# Shutdown_2019_v1_1_Power.net
KiCad netlist of a schematic drawn in Altium Designer
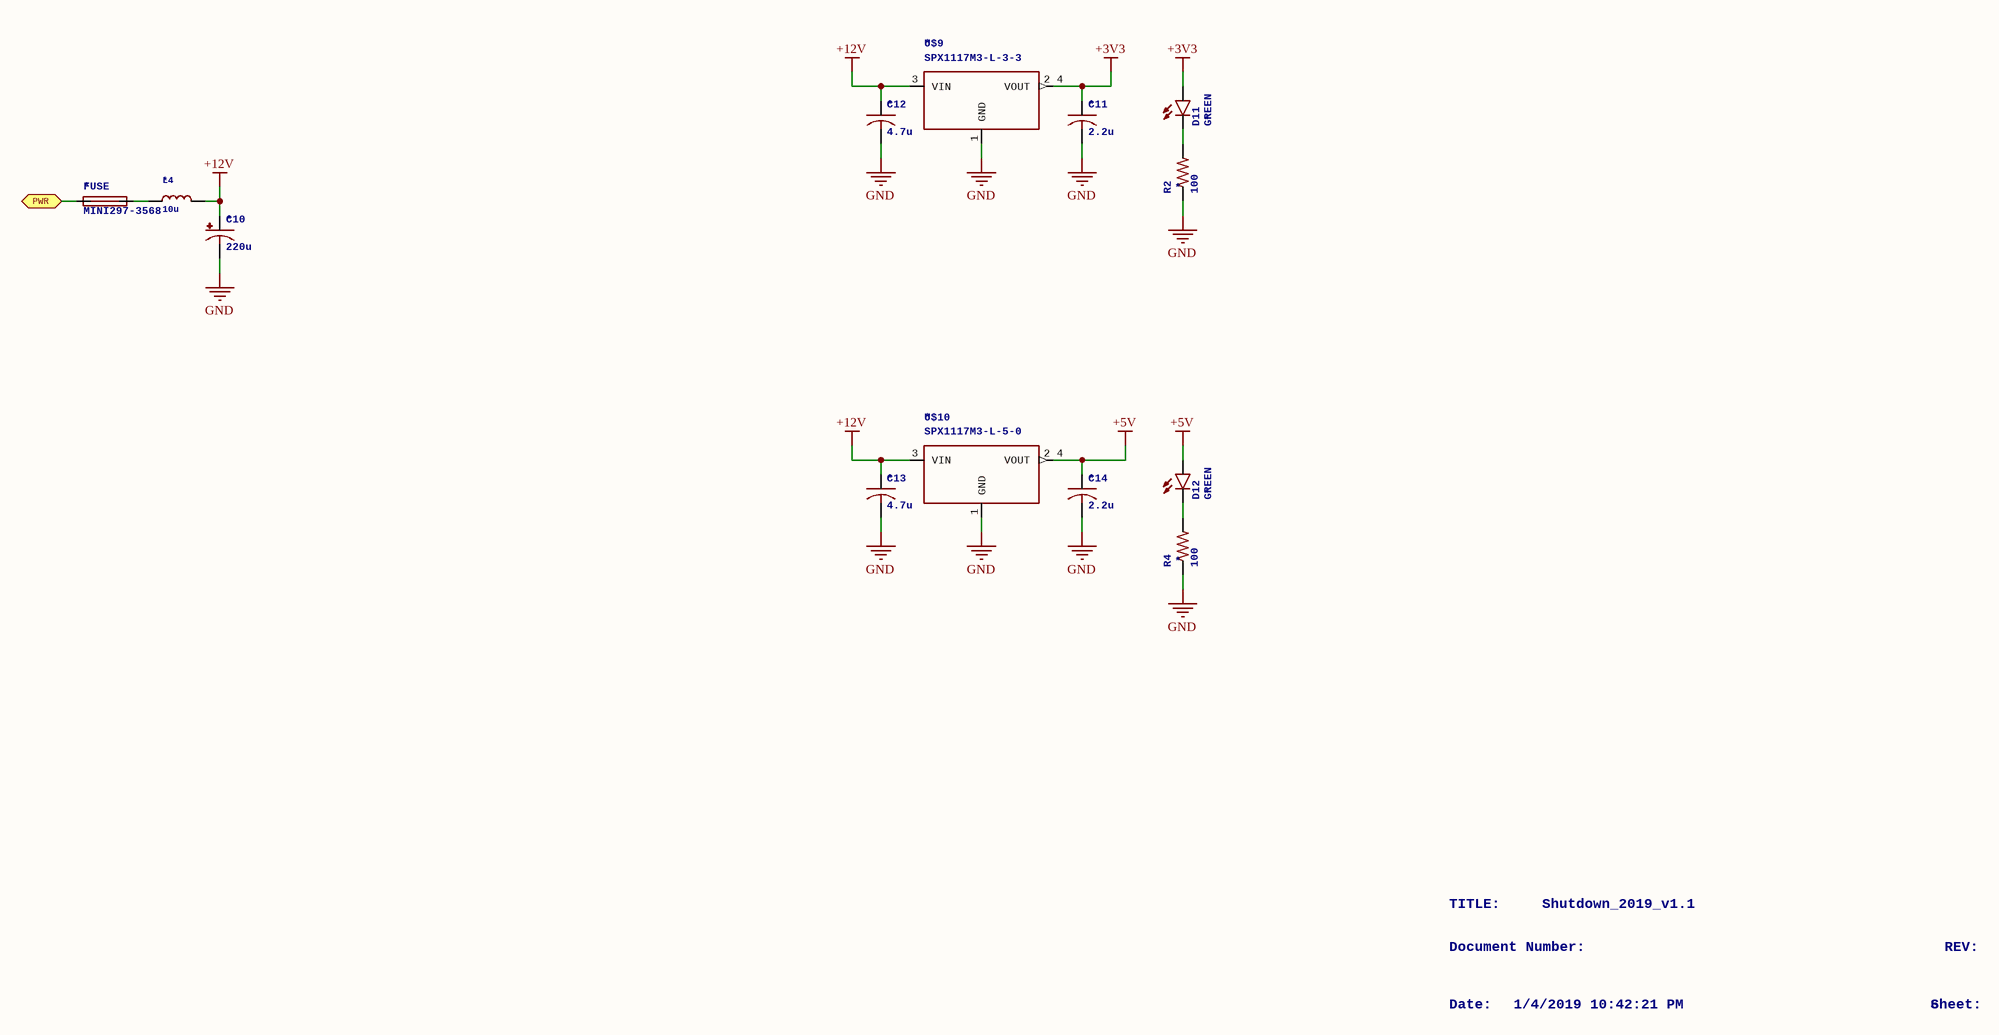
[diagram p0: Shutdown_2019_v1.1_Power.SchDoc]

(export (version "E")
  (design (tool "Eeschema 10.0.6"))
  (components
    (comp (ref "C10")
      (value "220u")
      (footprint "E2,5-7")
      (description "POLARIZED CAPACITOR, American symbol")
      (fields (field (name "NAME") "*"))
      (libsource (lib "rcl") (part "CPOL-USE2.5-7"))
    )
    (comp (ref "C11")
      (value "2.2u")
      (footprint "C0805")
      (description "CAPACITOR, American symbol")
      (fields (field (name "NAME") "*"))
      (libsource (lib "rcl") (part "C-USC0805"))
    )
    (comp (ref "C12")
      (value "4.7u")
      (footprint "C0805")
      (description "CAPACITOR, American symbol")
      (fields (field (name "NAME") "*"))
      (libsource (lib "rcl") (part "C-USC0805"))
    )
    (comp (ref "C13")
      (value "4.7u")
      (footprint "C0805")
      (description "CAPACITOR, American symbol")
      (fields (field (name "NAME") "*"))
      (libsource (lib "rcl") (part "C-USC0805"))
    )
    (comp (ref "C14")
      (value "2.2u")
      (footprint "C0805")
      (description "CAPACITOR, American symbol")
      (fields (field (name "NAME") "*"))
      (libsource (lib "rcl") (part "C-USC0805"))
    )
    (comp (ref "D11")
      (value "GREEN")
      (footprint "LED-0603")
      (fields (field (name "NAME") "*"))
      (libsource (lib "SparkFun-LED") (part "LED-GREEN0603"))
    )
    (comp (ref "D12")
      (value "GREEN")
      (footprint "LED-0603")
      (fields (field (name "NAME") "*"))
      (libsource (lib "SparkFun-LED") (part "LED-GREEN0603"))
    )
    (comp (ref "FUSE")
      (value "MINI297-3568")
      (footprint "3568")
      (fields (field (name "NAME") "*"))
      (libsource (lib "Fuse") (part "MINI297-3568"))
    )
    (comp (ref "L4")
      (value "10u")
      (footprint "INDUCTOR_5X5MM_NR5040_NOTHERMALS")
      (fields (field (name "NAME") "*"))
      (libsource (lib "microbuilder") (part "INDUCTORNR5040"))
    )
    (comp (ref "R2")
      (value "100")
      (footprint "R0603")
      (description "RESISTOR, American symbol")
      (fields (field (name "NAME") "*"))
      (libsource (lib "rcl") (part "R-US_R0603"))
    )
    (comp (ref "R4")
      (value "100")
      (footprint "R0603")
      (description "RESISTOR, American symbol")
      (fields (field (name "NAME") "*"))
      (libsource (lib "rcl") (part "R-US_R0603"))
    )
    (comp (ref "U$9")
      (value "SPX1117M3-L-3-3")
      (footprint "SOT223")
      (description "SPX1117M3-L-3-3 3.3V 800mA LDOMaxLinear IncDatasheetDigikey")
      (fields (field (name "NAME") "*"))
      (libsource (lib "MAXLINEAR") (part "SPX1117M3-L-3-3"))
    )
    (comp (ref "U$10")
      (value "SPX1117M3-L-5-0")
      (footprint "SOT223")
      (description "SPX1117M3-L-5-0 5.0V 800mA LDOMaxLinear IncDatasheetDigikey")
      (fields (field (name "NAME") "*"))
      (libsource (lib "MAXLINEAR") (part "SPX1117M3-L-5-0"))
    )
  )
  (nets
    (net (code "1") (name "+3V3") (class "Default")
      (node (ref "C11") (pin "1") (pinfunction "1_1") (pintype "passive"))
      (node (ref "D11") (pin "A") (pinfunction "A_A") (pintype "passive"))
      (node (ref "U$9") (pin "2_4") (pinfunction "VOUT_2_4") (pintype "output"))
    )
    (net (code "2") (name "+5V") (class "Default")
      (node (ref "C14") (pin "1") (pinfunction "1_1") (pintype "passive"))
      (node (ref "D12") (pin "A") (pinfunction "A_A") (pintype "passive"))
      (node (ref "U$10") (pin "2_4") (pinfunction "VOUT_2_4") (pintype "output"))
    )
    (net (code "3") (name "+12V") (class "Default")
      (node (ref "C10") (pin "+") (pinfunction "+_+") (pintype "passive"))
      (node (ref "C12") (pin "1") (pinfunction "1_1") (pintype "passive"))
      (node (ref "C13") (pin "1") (pinfunction "1_1") (pintype "passive"))
      (node (ref "L4") (pin "P$2") (pinfunction "2_P$2") (pintype "passive"))
      (node (ref "U$10") (pin "3") (pinfunction "VIN_3") (pintype "passive"))
      (node (ref "U$9") (pin "3") (pinfunction "VIN_3") (pintype "passive"))
    )
    (net (code "4") (name "/PWR") (class "Default")
      (node (ref "FUSE") (pin "P$1_P$4") (pinfunction "1_P$1_P$4") (pintype "passive"))
    )
    (net (code "5") (name "GND") (class "Default")
      (node (ref "C10") (pin "-") (pinfunction "-_-") (pintype "passive"))
      (node (ref "C11") (pin "2") (pinfunction "2_2") (pintype "passive"))
      (node (ref "C12") (pin "2") (pinfunction "2_2") (pintype "passive"))
      (node (ref "C13") (pin "2") (pinfunction "2_2") (pintype "passive"))
      (node (ref "C14") (pin "2") (pinfunction "2_2") (pintype "passive"))
      (node (ref "R2") (pin "1") (pinfunction "1_1") (pintype "passive"))
      (node (ref "R4") (pin "1") (pinfunction "1_1") (pintype "passive"))
      (node (ref "U$10") (pin "1") (pinfunction "GND_1") (pintype "passive"))
      (node (ref "U$9") (pin "1") (pinfunction "GND_1") (pintype "passive"))
    )
    (net (code "6") (name "Net-(D11-PadC)") (class "Default")
      (node (ref "D11") (pin "C") (pinfunction "C_C") (pintype "passive"))
      (node (ref "R2") (pin "2") (pinfunction "2_2") (pintype "passive"))
    )
    (net (code "7") (name "Net-(D12-PadC)") (class "Default")
      (node (ref "D12") (pin "C") (pinfunction "C_C") (pintype "passive"))
      (node (ref "R4") (pin "2") (pinfunction "2_2") (pintype "passive"))
    )
    (net (code "8") (name "Net-(FUSE-2)") (class "Default")
      (node (ref "FUSE") (pin "P$2_P$3") (pinfunction "2_P$2_P$3") (pintype "passive"))
      (node (ref "L4") (pin "P$1") (pinfunction "1_P$1") (pintype "passive"))
    )
  )
)
